# vactrolcrossfader.net
KiCad netlist of a schematic drawn in EAGLE
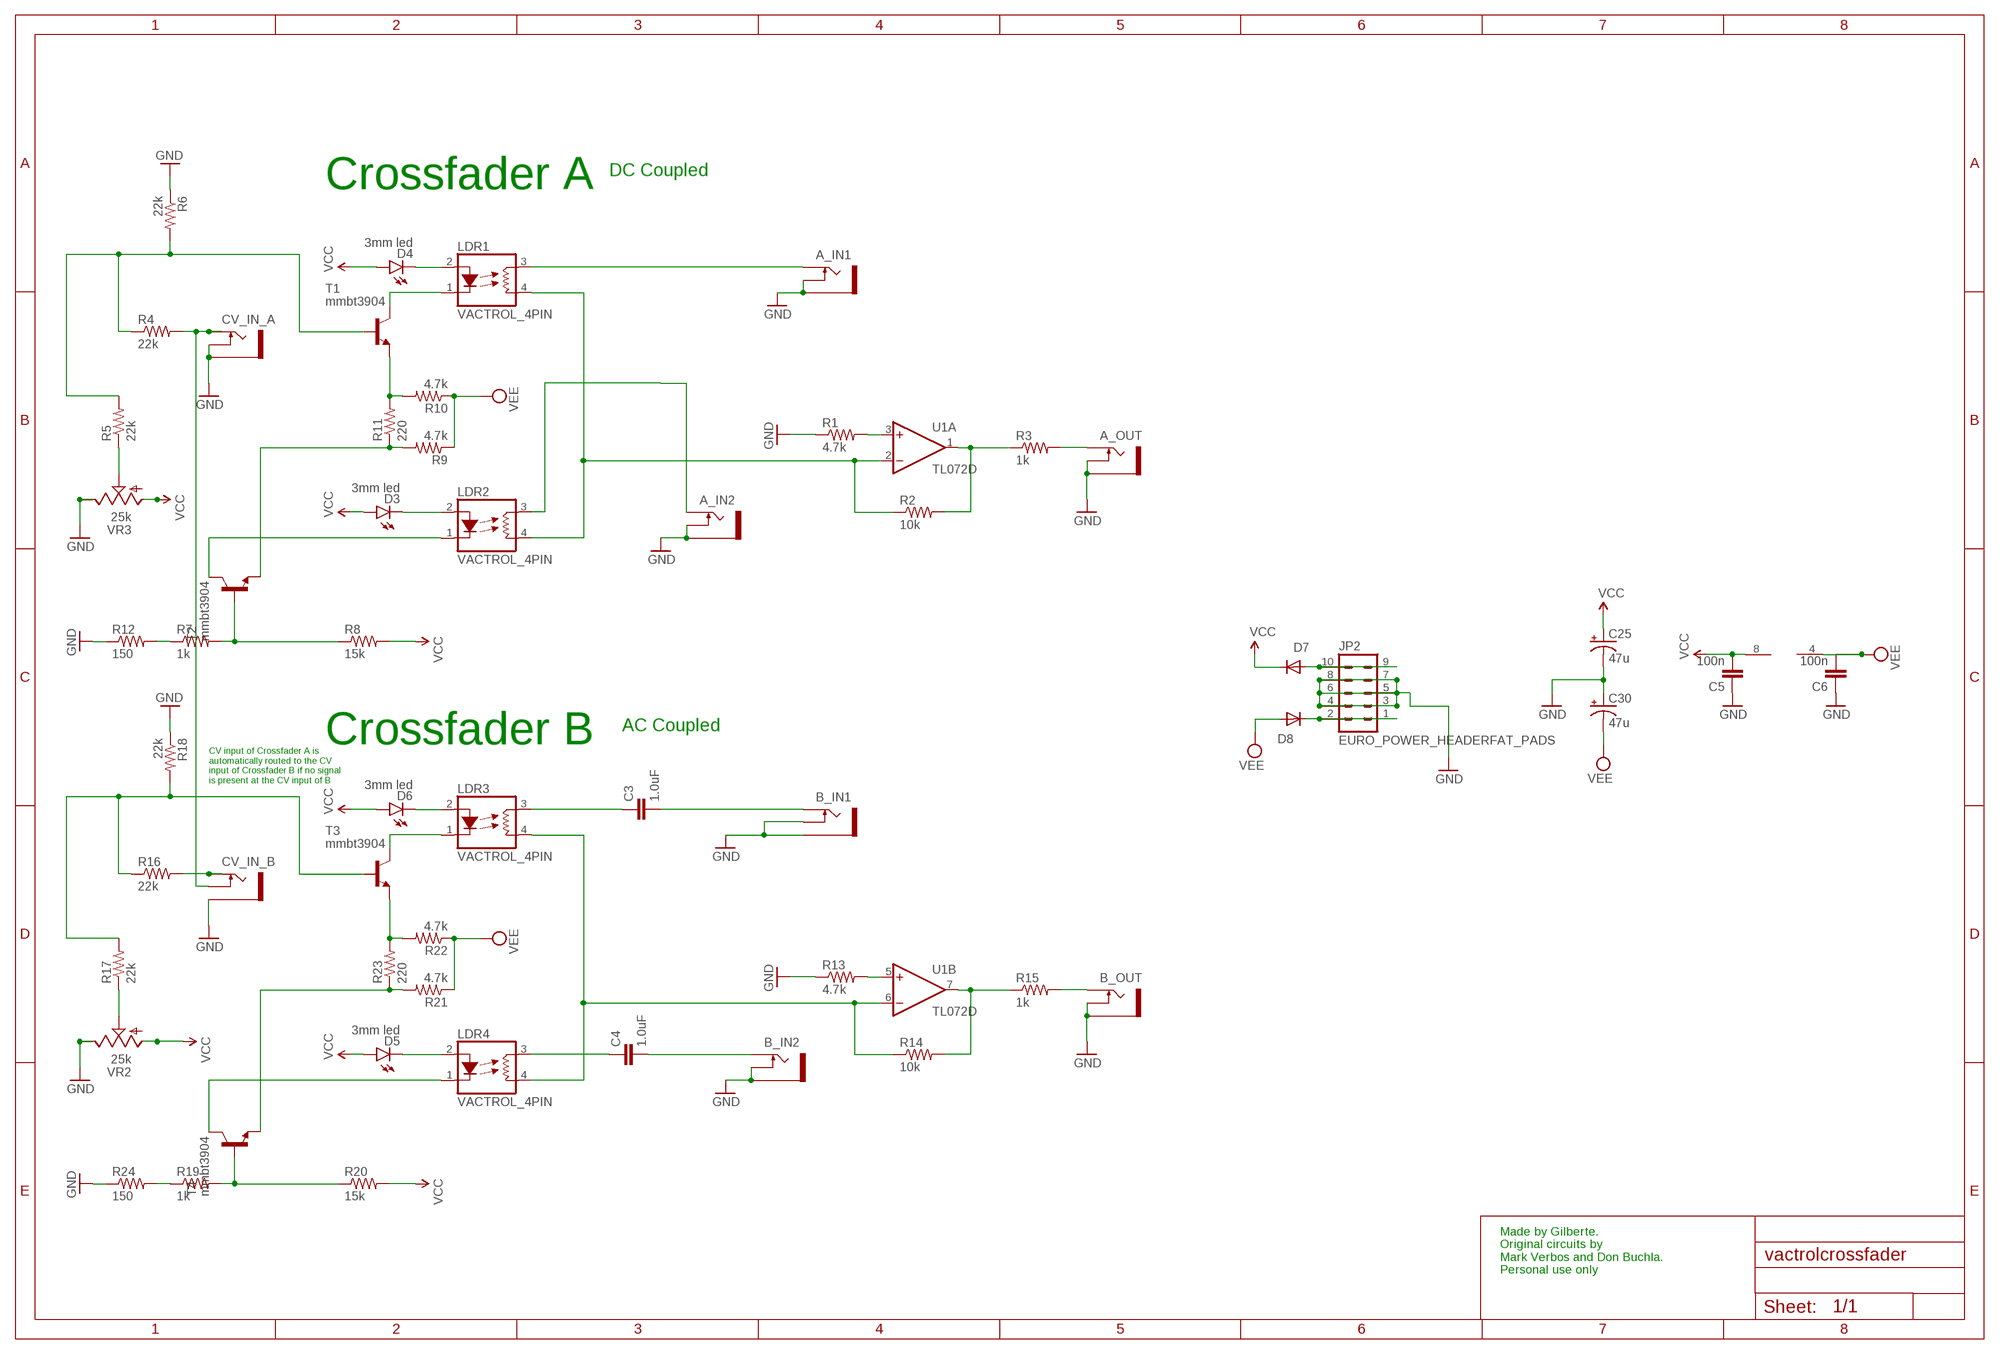
[diagram p0: schematic, sheet 1]

(export (version "E")
  (design (tool "Eeschema 10.0.6"))
  (components
    (comp (ref "A_IN1")
      (value "THONKICONNNEW")
      (footprint "eagle-import:WQP-PJ301M-12_JACK")
      (libsource (lib "eagle-import") (part "THONKICONNNEW"))
    )
    (comp (ref "A_IN2")
      (value "THONKICONNNEW")
      (footprint "eagle-import:WQP-PJ301M-12_JACK")
      (libsource (lib "eagle-import") (part "THONKICONNNEW"))
    )
    (comp (ref "A_OUT")
      (value "THONKICONNNEW")
      (footprint "eagle-import:WQP-PJ301M-12_JACK")
      (libsource (lib "eagle-import") (part "THONKICONNNEW"))
    )
    (comp (ref "B_IN1")
      (value "THONKICONNNEW")
      (footprint "eagle-import:WQP-PJ301M-12_JACK")
      (libsource (lib "eagle-import") (part "THONKICONNNEW"))
    )
    (comp (ref "B_IN2")
      (value "THONKICONNNEW")
      (footprint "eagle-import:WQP-PJ301M-12_JACK")
      (libsource (lib "eagle-import") (part "THONKICONNNEW"))
    )
    (comp (ref "B_OUT")
      (value "THONKICONNNEW")
      (footprint "eagle-import:WQP-PJ301M-12_JACK")
      (libsource (lib "eagle-import") (part "THONKICONNNEW"))
    )
    (comp (ref "C3")
      (value "1.0uF")
      (footprint "eagle-import:0805")
      (libsource (lib "eagle-import") (part "CAP0805"))
    )
    (comp (ref "C4")
      (value "1.0uF")
      (footprint "eagle-import:0805")
      (libsource (lib "eagle-import") (part "CAP0805"))
    )
    (comp (ref "C5")
      (value "100n")
      (footprint "eagle-import:0805")
      (libsource (lib "eagle-import") (part "CAP0805"))
    )
    (comp (ref "C6")
      (value "100n")
      (footprint "eagle-import:0805")
      (libsource (lib "eagle-import") (part "CAP0805"))
    )
    (comp (ref "C25")
      (value "47u")
      (footprint "eagle-import:PANASONIC_D")
      (libsource (lib "eagle-import") (part "CPOL-USD"))
    )
    (comp (ref "C30")
      (value "47u")
      (footprint "eagle-import:PANASONIC_D")
      (libsource (lib "eagle-import") (part "CPOL-USD"))
    )
    (comp (ref "CV_IN_A")
      (value "THONKICONNNEW")
      (footprint "eagle-import:WQP-PJ301M-12_JACK")
      (libsource (lib "eagle-import") (part "THONKICONNNEW"))
    )
    (comp (ref "CV_IN_B")
      (value "THONKICONNNEW")
      (footprint "eagle-import:WQP-PJ301M-12_JACK")
      (libsource (lib "eagle-import") (part "THONKICONNNEW"))
    )
    (comp (ref "D3")
      (value "3mm led")
      (footprint "eagle-import:LED3MM")
      (libsource (lib "eagle-import") (part "LED3MM"))
    )
    (comp (ref "D4")
      (value "3mm led")
      (footprint "eagle-import:LED3MM")
      (libsource (lib "eagle-import") (part "LED3MM"))
    )
    (comp (ref "D5")
      (value "3mm led")
      (footprint "eagle-import:LED3MM")
      (libsource (lib "eagle-import") (part "LED3MM"))
    )
    (comp (ref "D6")
      (value "3mm led")
      (footprint "eagle-import:LED3MM")
      (libsource (lib "eagle-import") (part "LED3MM"))
    )
    (comp (ref "D7")
      (value "1N5819HW")
      (footprint "eagle-import:SOD123")
      (libsource (lib "eagle-import") (part "DIODE-SOD123"))
    )
    (comp (ref "D8")
      (value "1N5819HW")
      (footprint "eagle-import:SOD123")
      (libsource (lib "eagle-import") (part "DIODE-SOD123"))
    )
    (comp (ref "JP2")
      (value "EURO_POWER_HEADERFAT_PADS")
      (footprint "eagle-import:EURO_PWR_HEADER_FAT")
      (libsource (lib "eagle-import") (part "EURO_POWER_HEADERFAT_PADS"))
    )
    (comp (ref "LDR1")
      (value "VACTROL_4PIN")
      (footprint "eagle-import:VACTROL_4PIN_VTL5C")
      (libsource (lib "eagle-import") (part "VACTROL_4PIN"))
    )
    (comp (ref "LDR2")
      (value "VACTROL_4PIN")
      (footprint "eagle-import:VACTROL_4PIN_VTL5C")
      (libsource (lib "eagle-import") (part "VACTROL_4PIN"))
    )
    (comp (ref "LDR3")
      (value "VACTROL_4PIN")
      (footprint "eagle-import:VACTROL_4PIN_VTL5C")
      (libsource (lib "eagle-import") (part "VACTROL_4PIN"))
    )
    (comp (ref "LDR4")
      (value "VACTROL_4PIN")
      (footprint "eagle-import:VACTROL_4PIN_VTL5C")
      (libsource (lib "eagle-import") (part "VACTROL_4PIN"))
    )
    (comp (ref "R1")
      (value "4.7k")
      (footprint "eagle-import:1206")
      (libsource (lib "eagle-import") (part "RESISTOR1206"))
    )
    (comp (ref "R2")
      (value "10k")
      (footprint "eagle-import:1206")
      (libsource (lib "eagle-import") (part "RESISTOR1206"))
    )
    (comp (ref "R3")
      (value "1k")
      (footprint "eagle-import:1206")
      (libsource (lib "eagle-import") (part "RESISTOR1206"))
    )
    (comp (ref "R4")
      (value "22k")
      (footprint "eagle-import:1206")
      (libsource (lib "eagle-import") (part "RESISTOR1206"))
    )
    (comp (ref "R5")
      (value "22k")
      (footprint "eagle-import:1206")
      (libsource (lib "eagle-import") (part "RESISTOR1206"))
    )
    (comp (ref "R6")
      (value "22k")
      (footprint "eagle-import:1206")
      (libsource (lib "eagle-import") (part "RESISTOR1206"))
    )
    (comp (ref "R7")
      (value "1k")
      (footprint "eagle-import:1206")
      (libsource (lib "eagle-import") (part "RESISTOR1206"))
    )
    (comp (ref "R8")
      (value "15k")
      (footprint "eagle-import:1206")
      (libsource (lib "eagle-import") (part "RESISTOR1206"))
    )
    (comp (ref "R9")
      (value "4.7k")
      (footprint "eagle-import:1206")
      (libsource (lib "eagle-import") (part "RESISTOR1206"))
    )
    (comp (ref "R10")
      (value "4.7k")
      (footprint "eagle-import:1206")
      (libsource (lib "eagle-import") (part "RESISTOR1206"))
    )
    (comp (ref "R11")
      (value "220")
      (footprint "eagle-import:1206")
      (libsource (lib "eagle-import") (part "RESISTOR1206"))
    )
    (comp (ref "R12")
      (value "150")
      (footprint "eagle-import:1206")
      (libsource (lib "eagle-import") (part "RESISTOR1206"))
    )
    (comp (ref "R13")
      (value "4.7k")
      (footprint "eagle-import:1206")
      (libsource (lib "eagle-import") (part "RESISTOR1206"))
    )
    (comp (ref "R14")
      (value "10k")
      (footprint "eagle-import:1206")
      (libsource (lib "eagle-import") (part "RESISTOR1206"))
    )
    (comp (ref "R15")
      (value "1k")
      (footprint "eagle-import:1206")
      (libsource (lib "eagle-import") (part "RESISTOR1206"))
    )
    (comp (ref "R16")
      (value "22k")
      (footprint "eagle-import:1206")
      (libsource (lib "eagle-import") (part "RESISTOR1206"))
    )
    (comp (ref "R17")
      (value "22k")
      (footprint "eagle-import:1206")
      (libsource (lib "eagle-import") (part "RESISTOR1206"))
    )
    (comp (ref "R18")
      (value "22k")
      (footprint "eagle-import:1206")
      (libsource (lib "eagle-import") (part "RESISTOR1206"))
    )
    (comp (ref "R19")
      (value "1k")
      (footprint "eagle-import:1206")
      (libsource (lib "eagle-import") (part "RESISTOR1206"))
    )
    (comp (ref "R20")
      (value "15k")
      (footprint "eagle-import:1206")
      (libsource (lib "eagle-import") (part "RESISTOR1206"))
    )
    (comp (ref "R21")
      (value "4.7k")
      (footprint "eagle-import:1206")
      (libsource (lib "eagle-import") (part "RESISTOR1206"))
    )
    (comp (ref "R22")
      (value "4.7k")
      (footprint "eagle-import:1206")
      (libsource (lib "eagle-import") (part "RESISTOR1206"))
    )
    (comp (ref "R23")
      (value "220")
      (footprint "eagle-import:1206")
      (libsource (lib "eagle-import") (part "RESISTOR1206"))
    )
    (comp (ref "R24")
      (value "150")
      (footprint "eagle-import:1206")
      (libsource (lib "eagle-import") (part "RESISTOR1206"))
    )
    (comp (ref "T1")
      (value "mmbt3904")
      (footprint "eagle-import:SOT23-BEC")
      (libsource (lib "eagle-import") (part "-NPN-SOT23-BECMMBT3904LT1"))
    )
    (comp (ref "T2")
      (value "mmbt3904")
      (footprint "eagle-import:SOT23-BEC")
      (libsource (lib "eagle-import") (part "-NPN-SOT23-BECMMBT3904LT1"))
    )
    (comp (ref "T3")
      (value "mmbt3904")
      (footprint "eagle-import:SOT23-BEC")
      (libsource (lib "eagle-import") (part "-NPN-SOT23-BECMMBT3904LT1"))
    )
    (comp (ref "T4")
      (value "mmbt3904")
      (footprint "eagle-import:SOT23-BEC")
      (libsource (lib "eagle-import") (part "-NPN-SOT23-BECMMBT3904LT1"))
    )
    (comp (ref "U1")
      (value "TL072D")
      (footprint "eagle-import:SO08")
      (libsource (lib "eagle-import") (part "TL072D"))
    )
    (comp (ref "VR2")
      (value "25k")
      (footprint "eagle-import:9MM_SNAP-IN_POT")
      (libsource (lib "eagle-import") (part "9MM_SNAP-IN_POT_"))
    )
    (comp (ref "VR3")
      (value "25k")
      (footprint "eagle-import:9MM_SNAP-IN_POT")
      (libsource (lib "eagle-import") (part "9MM_SNAP-IN_POT_"))
    )
  )
  (nets
    (net (code "1") (name "GND") (class "Default")
      (node (ref "A_IN1") (pin "P$2_SWITCH") (pinfunction "SWITCH_P$2_SWITCH") (pintype "passive"))
      (node (ref "A_IN1") (pin "P$3_SLEEVE") (pinfunction "SLEEVE_P$3_SLEEVE") (pintype "passive"))
      (node (ref "A_IN2") (pin "P$2_SWITCH") (pinfunction "SWITCH_P$2_SWITCH") (pintype "passive"))
      (node (ref "A_IN2") (pin "P$3_SLEEVE") (pinfunction "SLEEVE_P$3_SLEEVE") (pintype "passive"))
      (node (ref "A_OUT") (pin "P$2_SWITCH") (pinfunction "SWITCH_P$2_SWITCH") (pintype "passive"))
      (node (ref "A_OUT") (pin "P$3_SLEEVE") (pinfunction "SLEEVE_P$3_SLEEVE") (pintype "passive"))
      (node (ref "B_IN1") (pin "P$2_SWITCH") (pinfunction "SWITCH_P$2_SWITCH") (pintype "passive"))
      (node (ref "B_IN1") (pin "P$3_SLEEVE") (pinfunction "SLEEVE_P$3_SLEEVE") (pintype "passive"))
      (node (ref "B_IN2") (pin "P$2_SWITCH") (pinfunction "SWITCH_P$2_SWITCH") (pintype "passive"))
      (node (ref "B_IN2") (pin "P$3_SLEEVE") (pinfunction "SLEEVE_P$3_SLEEVE") (pintype "passive"))
      (node (ref "B_OUT") (pin "P$2_SWITCH") (pinfunction "SWITCH_P$2_SWITCH") (pintype "passive"))
      (node (ref "B_OUT") (pin "P$3_SLEEVE") (pinfunction "SLEEVE_P$3_SLEEVE") (pintype "passive"))
      (node (ref "C25") (pin "-") (pinfunction "-_-") (pintype "passive"))
      (node (ref "C30") (pin "+") (pinfunction "+_+") (pintype "passive"))
      (node (ref "C5") (pin "1") (pinfunction "1_1") (pintype "passive"))
      (node (ref "C6") (pin "1") (pinfunction "1_1") (pintype "passive"))
      (node (ref "CV_IN_A") (pin "P$2_SWITCH") (pinfunction "SWITCH_P$2_SWITCH") (pintype "passive"))
      (node (ref "CV_IN_A") (pin "P$3_SLEEVE") (pinfunction "SLEEVE_P$3_SLEEVE") (pintype "passive"))
      (node (ref "CV_IN_B") (pin "P$3_SLEEVE") (pinfunction "SLEEVE_P$3_SLEEVE") (pintype "passive"))
      (node (ref "JP2") (pin "3") (pinfunction "3_3") (pintype "passive"))
      (node (ref "JP2") (pin "4") (pinfunction "4_4") (pintype "passive"))
      (node (ref "JP2") (pin "5") (pinfunction "5_5") (pintype "passive"))
      (node (ref "JP2") (pin "6") (pinfunction "6_6") (pintype "passive"))
      (node (ref "JP2") (pin "7") (pinfunction "7_7") (pintype "passive"))
      (node (ref "JP2") (pin "8") (pinfunction "8_8") (pintype "passive"))
      (node (ref "R1") (pin "1") (pinfunction "1_1") (pintype "passive"))
      (node (ref "R12") (pin "1") (pinfunction "1_1") (pintype "passive"))
      (node (ref "R13") (pin "1") (pinfunction "1_1") (pintype "passive"))
      (node (ref "R18") (pin "1") (pinfunction "1_1") (pintype "passive"))
      (node (ref "R24") (pin "1") (pinfunction "1_1") (pintype "passive"))
      (node (ref "R6") (pin "1") (pinfunction "1_1") (pintype "passive"))
      (node (ref "VR2") (pin "3") (pinfunction "E_3") (pintype "passive"))
      (node (ref "VR3") (pin "3") (pinfunction "E_3") (pintype "passive"))
    )
    (net (code "2") (name "Net-(A_IN1-TIP)") (class "Default")
      (node (ref "A_IN1") (pin "P$1_TIP") (pinfunction "TIP_P$1_TIP") (pintype "passive"))
      (node (ref "LDR1") (pin "3") (pinfunction "RES1_3") (pintype "passive"))
    )
    (net (code "3") (name "Net-(A_IN2-TIP)") (class "Default")
      (node (ref "A_IN2") (pin "P$1_TIP") (pinfunction "TIP_P$1_TIP") (pintype "passive"))
      (node (ref "LDR2") (pin "3") (pinfunction "RES1_3") (pintype "passive"))
    )
    (net (code "4") (name "Net-(A_OUT-TIP)") (class "Default")
      (node (ref "A_OUT") (pin "P$1_TIP") (pinfunction "TIP_P$1_TIP") (pintype "passive"))
      (node (ref "R3") (pin "2") (pinfunction "2_2") (pintype "passive"))
    )
    (net (code "5") (name "Net-(B_IN1-TIP)") (class "Default")
      (node (ref "B_IN1") (pin "P$1_TIP") (pinfunction "TIP_P$1_TIP") (pintype "passive"))
      (node (ref "C3") (pin "2") (pinfunction "2_2") (pintype "passive"))
    )
    (net (code "6") (name "Net-(B_IN2-TIP)") (class "Default")
      (node (ref "B_IN2") (pin "P$1_TIP") (pinfunction "TIP_P$1_TIP") (pintype "passive"))
      (node (ref "C4") (pin "2") (pinfunction "2_2") (pintype "passive"))
    )
    (net (code "7") (name "Net-(B_OUT-TIP)") (class "Default")
      (node (ref "B_OUT") (pin "P$1_TIP") (pinfunction "TIP_P$1_TIP") (pintype "passive"))
      (node (ref "R15") (pin "2") (pinfunction "2_2") (pintype "passive"))
    )
    (net (code "8") (name "Net-(CV_IN_A-TIP)") (class "Default")
      (node (ref "CV_IN_A") (pin "P$1_TIP") (pinfunction "TIP_P$1_TIP") (pintype "passive"))
      (node (ref "CV_IN_B") (pin "P$2_SWITCH") (pinfunction "SWITCH_P$2_SWITCH") (pintype "passive"))
      (node (ref "R4") (pin "2") (pinfunction "2_2") (pintype "passive"))
    )
    (net (code "9") (name "Net-(CV_IN_B-TIP)") (class "Default")
      (node (ref "CV_IN_B") (pin "P$1_TIP") (pinfunction "TIP_P$1_TIP") (pintype "passive"))
      (node (ref "R16") (pin "2") (pinfunction "2_2") (pintype "passive"))
    )
    (net (code "10") (name "Net-(D3-C)") (class "Default")
      (node (ref "D3") (pin "K") (pinfunction "C_K") (pintype "passive"))
      (node (ref "LDR2") (pin "2") (pinfunction "LED+_2") (pintype "passive"))
    )
    (net (code "11") (name "Net-(D4-C)") (class "Default")
      (node (ref "D4") (pin "K") (pinfunction "C_K") (pintype "passive"))
      (node (ref "LDR1") (pin "2") (pinfunction "LED+_2") (pintype "passive"))
    )
    (net (code "12") (name "Net-(D5-C)") (class "Default")
      (node (ref "D5") (pin "K") (pinfunction "C_K") (pintype "passive"))
      (node (ref "LDR4") (pin "2") (pinfunction "LED+_2") (pintype "passive"))
    )
    (net (code "13") (name "Net-(D6-C)") (class "Default")
      (node (ref "D6") (pin "K") (pinfunction "C_K") (pintype "passive"))
      (node (ref "LDR3") (pin "2") (pinfunction "LED+_2") (pintype "passive"))
    )
    (net (code "14") (name "Net-(D7-PadA)") (class "Default")
      (node (ref "D7") (pin "A") (pinfunction "A_A") (pintype "passive"))
      (node (ref "JP2") (pin "10") (pinfunction "10_10") (pintype "passive"))
      (node (ref "JP2") (pin "9") (pinfunction "9_9") (pintype "passive"))
    )
    (net (code "15") (name "Net-(D8-PadC)") (class "Default")
      (node (ref "D8") (pin "C") (pinfunction "C_C") (pintype "passive"))
      (node (ref "JP2") (pin "1") (pinfunction "1_1") (pintype "passive"))
      (node (ref "JP2") (pin "2") (pinfunction "2_2") (pintype "passive"))
    )
    (net (code "16") (name "Net-(LDR1-LED-)") (class "Default")
      (node (ref "LDR1") (pin "1") (pinfunction "LED-_1") (pintype "passive"))
      (node (ref "T1") (pin "C") (pinfunction "C_C") (pintype "passive"))
    )
    (net (code "17") (name "Net-(LDR1-RES2)") (class "Default")
      (node (ref "LDR1") (pin "4") (pinfunction "RES2_4") (pintype "passive"))
      (node (ref "LDR2") (pin "4") (pinfunction "RES2_4") (pintype "passive"))
      (node (ref "R2") (pin "1") (pinfunction "1_1") (pintype "passive"))
      (node (ref "U1") (pin "2") (pinfunction "-IN_2") (pintype "input"))
    )
    (net (code "18") (name "Net-(LDR2-LED-)") (class "Default")
      (node (ref "LDR2") (pin "1") (pinfunction "LED-_1") (pintype "passive"))
      (node (ref "T2") (pin "C") (pinfunction "C_C") (pintype "passive"))
    )
    (net (code "19") (name "Net-(LDR3-LED-)") (class "Default")
      (node (ref "LDR3") (pin "1") (pinfunction "LED-_1") (pintype "passive"))
      (node (ref "T3") (pin "C") (pinfunction "C_C") (pintype "passive"))
    )
    (net (code "20") (name "Net-(LDR3-RES1)") (class "Default")
      (node (ref "C3") (pin "1") (pinfunction "1_1") (pintype "passive"))
      (node (ref "LDR3") (pin "3") (pinfunction "RES1_3") (pintype "passive"))
    )
    (net (code "21") (name "Net-(LDR3-RES2)") (class "Default")
      (node (ref "LDR3") (pin "4") (pinfunction "RES2_4") (pintype "passive"))
      (node (ref "LDR4") (pin "4") (pinfunction "RES2_4") (pintype "passive"))
      (node (ref "R14") (pin "1") (pinfunction "1_1") (pintype "passive"))
      (node (ref "U1") (pin "6") (pinfunction "-IN_6") (pintype "input"))
    )
    (net (code "22") (name "Net-(LDR4-LED-)") (class "Default")
      (node (ref "LDR4") (pin "1") (pinfunction "LED-_1") (pintype "passive"))
      (node (ref "T4") (pin "C") (pinfunction "C_C") (pintype "passive"))
    )
    (net (code "23") (name "Net-(LDR4-RES1)") (class "Default")
      (node (ref "C4") (pin "1") (pinfunction "1_1") (pintype "passive"))
      (node (ref "LDR4") (pin "3") (pinfunction "RES1_3") (pintype "passive"))
    )
    (net (code "24") (name "Net-(R4-Pad1)") (class "Default")
      (node (ref "R4") (pin "1") (pinfunction "1_1") (pintype "passive"))
      (node (ref "R5") (pin "2") (pinfunction "2_2") (pintype "passive"))
      (node (ref "R6") (pin "2") (pinfunction "2_2") (pintype "passive"))
      (node (ref "T1") (pin "B") (pinfunction "B_B") (pintype "passive"))
    )
    (net (code "25") (name "Net-(R7-Pad2)") (class "Default")
      (node (ref "R7") (pin "2") (pinfunction "2_2") (pintype "passive"))
      (node (ref "R8") (pin "1") (pinfunction "1_1") (pintype "passive"))
      (node (ref "T2") (pin "B") (pinfunction "B_B") (pintype "passive"))
    )
    (net (code "26") (name "Net-(R10-Pad2)") (class "Default")
      (node (ref "R10") (pin "2") (pinfunction "2_2") (pintype "passive"))
      (node (ref "R11") (pin "2") (pinfunction "2_2") (pintype "passive"))
      (node (ref "T1") (pin "E") (pinfunction "E_E") (pintype "passive"))
    )
    (net (code "27") (name "Net-(R11-Pad1)") (class "Default")
      (node (ref "R11") (pin "1") (pinfunction "1_1") (pintype "passive"))
      (node (ref "R9") (pin "2") (pinfunction "2_2") (pintype "passive"))
      (node (ref "T2") (pin "E") (pinfunction "E_E") (pintype "passive"))
    )
    (net (code "28") (name "Net-(R12-Pad2)") (class "Default")
      (node (ref "R12") (pin "2") (pinfunction "2_2") (pintype "passive"))
      (node (ref "R7") (pin "1") (pinfunction "1_1") (pintype "passive"))
    )
    (net (code "29") (name "Net-(R16-Pad1)") (class "Default")
      (node (ref "R16") (pin "1") (pinfunction "1_1") (pintype "passive"))
      (node (ref "R17") (pin "2") (pinfunction "2_2") (pintype "passive"))
      (node (ref "R18") (pin "2") (pinfunction "2_2") (pintype "passive"))
      (node (ref "T3") (pin "B") (pinfunction "B_B") (pintype "passive"))
    )
    (net (code "30") (name "Net-(R19-Pad1)") (class "Default")
      (node (ref "R19") (pin "1") (pinfunction "1_1") (pintype "passive"))
      (node (ref "R24") (pin "2") (pinfunction "2_2") (pintype "passive"))
    )
    (net (code "31") (name "Net-(R19-Pad2)") (class "Default")
      (node (ref "R19") (pin "2") (pinfunction "2_2") (pintype "passive"))
      (node (ref "R20") (pin "1") (pinfunction "1_1") (pintype "passive"))
      (node (ref "T4") (pin "B") (pinfunction "B_B") (pintype "passive"))
    )
    (net (code "32") (name "Net-(R21-Pad2)") (class "Default")
      (node (ref "R21") (pin "2") (pinfunction "2_2") (pintype "passive"))
      (node (ref "R23") (pin "1") (pinfunction "1_1") (pintype "passive"))
      (node (ref "T4") (pin "E") (pinfunction "E_E") (pintype "passive"))
    )
    (net (code "33") (name "Net-(R22-Pad2)") (class "Default")
      (node (ref "R22") (pin "2") (pinfunction "2_2") (pintype "passive"))
      (node (ref "R23") (pin "2") (pinfunction "2_2") (pintype "passive"))
      (node (ref "T3") (pin "E") (pinfunction "E_E") (pintype "passive"))
    )
    (net (code "34") (name "Net-(U1A-+IN)") (class "Default")
      (node (ref "R1") (pin "2") (pinfunction "2_2") (pintype "passive"))
      (node (ref "U1") (pin "3") (pinfunction "+IN_3") (pintype "input"))
    )
    (net (code "35") (name "Net-(U1A-OUT)") (class "Default")
      (node (ref "R2") (pin "2") (pinfunction "2_2") (pintype "passive"))
      (node (ref "R3") (pin "1") (pinfunction "1_1") (pintype "passive"))
      (node (ref "U1") (pin "1") (pinfunction "OUT_1") (pintype "output"))
    )
    (net (code "36") (name "Net-(U1B-+IN)") (class "Default")
      (node (ref "R13") (pin "2") (pinfunction "2_2") (pintype "passive"))
      (node (ref "U1") (pin "5") (pinfunction "+IN_5") (pintype "input"))
    )
    (net (code "37") (name "Net-(U1B-OUT)") (class "Default")
      (node (ref "R14") (pin "2") (pinfunction "2_2") (pintype "passive"))
      (node (ref "R15") (pin "1") (pinfunction "1_1") (pintype "passive"))
      (node (ref "U1") (pin "7") (pinfunction "OUT_7") (pintype "output"))
    )
    (net (code "38") (name "Net-(VR2-S)") (class "Default")
      (node (ref "R17") (pin "1") (pinfunction "1_1") (pintype "passive"))
      (node (ref "VR2") (pin "2") (pinfunction "S_2") (pintype "passive"))
    )
    (net (code "39") (name "Net-(VR3-S)") (class "Default")
      (node (ref "R5") (pin "1") (pinfunction "1_1") (pintype "passive"))
      (node (ref "VR3") (pin "2") (pinfunction "S_2") (pintype "passive"))
    )
    (net (code "40") (name "VCC") (class "Default")
      (node (ref "C25") (pin "+") (pinfunction "+_+") (pintype "passive"))
      (node (ref "C5") (pin "2") (pinfunction "2_2") (pintype "passive"))
      (node (ref "D3") (pin "A") (pinfunction "A_A") (pintype "passive"))
      (node (ref "D4") (pin "A") (pinfunction "A_A") (pintype "passive"))
      (node (ref "D5") (pin "A") (pinfunction "A_A") (pintype "passive"))
      (node (ref "D6") (pin "A") (pinfunction "A_A") (pintype "passive"))
      (node (ref "D7") (pin "C") (pinfunction "C_C") (pintype "passive"))
      (node (ref "R20") (pin "2") (pinfunction "2_2") (pintype "passive"))
      (node (ref "R8") (pin "2") (pinfunction "2_2") (pintype "passive"))
      (node (ref "U1") (pin "8") (pinfunction "V+_8") (pintype "power_in"))
      (node (ref "VR2") (pin "1") (pinfunction "A_1") (pintype "passive"))
      (node (ref "VR3") (pin "1") (pinfunction "A_1") (pintype "passive"))
    )
    (net (code "41") (name "VEE") (class "Default")
      (node (ref "C30") (pin "-") (pinfunction "-_-") (pintype "passive"))
      (node (ref "C6") (pin "2") (pinfunction "2_2") (pintype "passive"))
      (node (ref "D8") (pin "A") (pinfunction "A_A") (pintype "passive"))
      (node (ref "R10") (pin "1") (pinfunction "1_1") (pintype "passive"))
      (node (ref "R21") (pin "1") (pinfunction "1_1") (pintype "passive"))
      (node (ref "R22") (pin "1") (pinfunction "1_1") (pintype "passive"))
      (node (ref "R9") (pin "1") (pinfunction "1_1") (pintype "passive"))
      (node (ref "U1") (pin "4") (pinfunction "V-_4") (pintype "power_in"))
    )
  )
)
